# PM6680_OCXO.net
KiCad netlist of a schematic drawn in Altium Designer
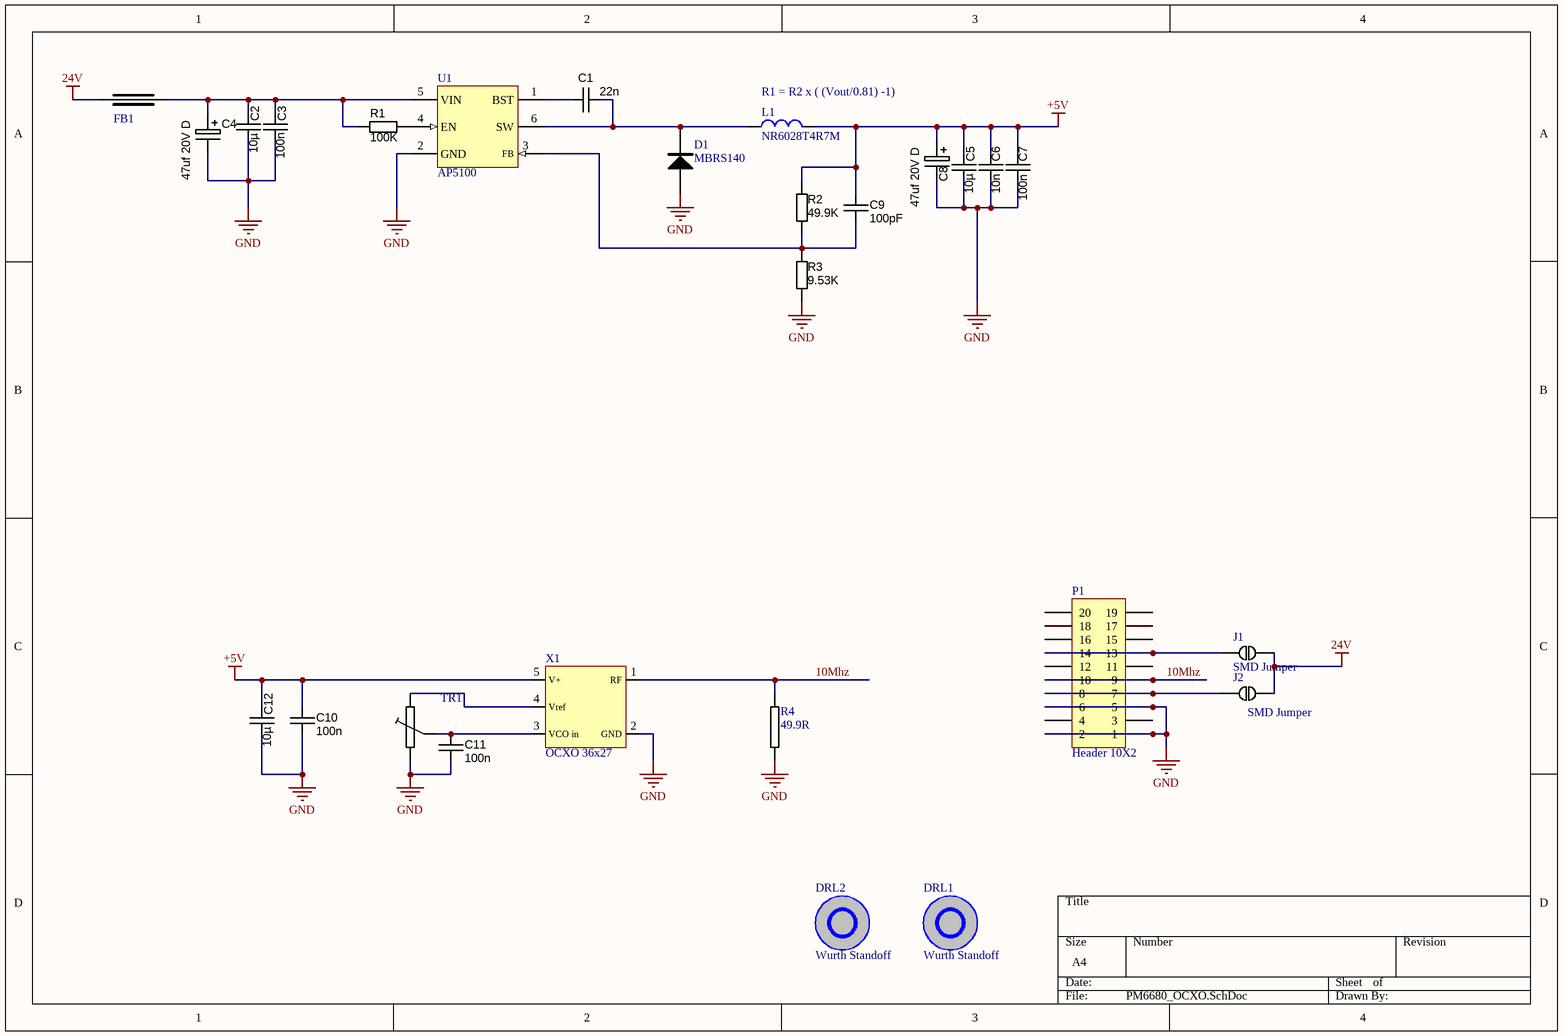
[diagram p0: PM6680_OCXO.SchDoc]

(export (version "E")
  (design (tool "Eeschema 10.0.6"))
  (components
    (comp (ref "C1")
      (value "22n")
      (footprint "CAPC1608N")
      (description "Capacitor SMD Cer 10pF 5% 50V NP0 0603")
      (fields (field (name "TOLERANCE") "±5%") (field (name "PART") "C0603X104K5RAC"))
      (libsource (lib "PBL - Capacitors") (part "CAPC_10p_0603_NP0_1%_50V"))
    )
    (comp (ref "C2")
      (value "10µ")
      (footprint "CAPC3225N")
      (description "Capacitor SMD Cer 10uF 20% 16V X5R 1210")
      (fields (field (name "TOLERANCE") "±20%"))
      (libsource (lib "PBL - Capacitors") (part "CAPC_10u_1210_50V"))
    )
    (comp (ref "C3")
      (value "100n")
      (footprint "CAPC1608N")
      (description "Capacitor SMD Cer 10pF 5% 50V NP0 0603")
      (fields (field (name "TOLERANCE") "±5%") (field (name "PART") "C0603X104K5RAC"))
      (libsource (lib "PBL - Capacitors") (part "CAPC_10p_0603_NP0_1%_50V"))
    )
    (comp (ref "C4")
      (value "47uf 20V D")
      (footprint "CAPMP7343X310N")
      (description "Capacitor SMD Tant 330uF 20% 6V3 2917")
      (fields
        (field (name "TOLERANCE") "±20%")
        (field (name "MANUFACTURER PART NUMBER") "T520D337M006ATE015")
      )
      (libsource (lib "PBL - Capacitors") (part "CAPT_330u_2917_6V3"))
    )
    (comp (ref "C5")
      (value "10µ")
      (footprint "CAPC3225N")
      (description "Capacitor SMD Cer 10uF 20% 16V X5R 1210")
      (fields (field (name "TOLERANCE") "±20%"))
      (libsource (lib "PBL - Capacitors") (part "CAPC_10u_1210_50V"))
    )
    (comp (ref "C6")
      (value "10n")
      (footprint "CAPC1608N")
      (description "Capacitor SMD Cer 10pF 5% 50V NP0 0603")
      (fields (field (name "TOLERANCE") "±5%") (field (name "PART") "C0603X104K5RAC"))
      (libsource (lib "PBL - Capacitors") (part "CAPC_10p_0603_NP0_1%_50V"))
    )
    (comp (ref "C7")
      (value "100n")
      (footprint "CAPC1608N")
      (description "Capacitor SMD Cer 10pF 5% 50V NP0 0603")
      (fields (field (name "TOLERANCE") "±5%") (field (name "PART") "C0603X104K5RAC"))
      (libsource (lib "PBL - Capacitors") (part "CAPC_10p_0603_NP0_1%_50V"))
    )
    (comp (ref "C8")
      (value "47uf 20V D")
      (footprint "CAPMP7343X310N")
      (description "Capacitor SMD Tant 330uF 20% 6V3 2917")
      (fields
        (field (name "TOLERANCE") "±20%")
        (field (name "MANUFACTURER PART NUMBER") "T520D337M006ATE015")
      )
      (libsource (lib "PBL - Capacitors") (part "CAPT_330u_2917_6V3"))
    )
    (comp (ref "C9")
      (value "100pF")
      (footprint "CAPC1608N")
      (description "Capacitor SMD Cer 10pF 5% 50V NP0 0603")
      (fields (field (name "TOLERANCE") "±5%") (field (name "PART") "C0603X104K5RAC"))
      (libsource (lib "PBL - Capacitors") (part "CAPC_10p_0603_NP0_1%_50V"))
    )
    (comp (ref "C10")
      (value "100n")
      (footprint "CAPC1608N")
      (description "Capacitor SMD Cer 10pF 5% 50V NP0 0603")
      (fields (field (name "TOLERANCE") "±5%") (field (name "PART") "C0603X104K5RAC"))
      (libsource (lib "PBL - Capacitors") (part "CAPC_10p_0603_NP0_1%_50V"))
    )
    (comp (ref "C11")
      (value "100n")
      (footprint "CAPC1608N")
      (description "Capacitor SMD Cer 10pF 5% 50V NP0 0603")
      (fields (field (name "TOLERANCE") "±5%") (field (name "PART") "C0603X104K5RAC"))
      (libsource (lib "PBL - Capacitors") (part "CAPC_10p_0603_NP0_1%_50V"))
    )
    (comp (ref "C12")
      (value "10µ")
      (footprint "CAPC3225N")
      (description "Capacitor SMD Cer 10uF 20% 16V X5R 1210")
      (fields (field (name "TOLERANCE") "±20%"))
      (libsource (lib "PBL - Capacitors") (part "CAPC_10u_1210_50V"))
    )
    (comp (ref "D1")
      (value "MBRS140")
      (footprint "DIODE-SMA")
      (description "DIODE")
      (libsource (lib "Generic") (part "MBRS140"))
    )
    (comp (ref "DRL1")
      (value "Wurth Standoff")
      (footprint "Wurth_PCB_STANDOFF_7740_6mm")
      (fields (field (name "PART") "9774050360"))
      (libsource (lib "cvlib") (part "PCB_Sandoff"))
    )
    (comp (ref "DRL2")
      (value "Wurth Standoff")
      (footprint "Wurth_PCB_STANDOFF_7740_6mm")
      (fields (field (name "PART") "9774050360"))
      (libsource (lib "cvlib") (part "PCB_Sandoff"))
    )
    (comp (ref "FB1")
      (value "~")
      (footprint "0805FB-600Z")
      (description "FERRITE BEAD 600 OHM 2A")
      (fields (field (name "PART") "ILHB0805ER300V"))
      (libsource (lib "Generic") (part "0805FB-600Z"))
    )
    (comp (ref "J1")
      (value "SMD Jumper")
      (footprint "SMD_Jumper")
      (libsource (lib "cvlib") (part "SMD_Jumper"))
    )
    (comp (ref "J2")
      (value "SMD Jumper")
      (footprint "SMD_Jumper")
      (libsource (lib "cvlib") (part "SMD_Jumper"))
    )
    (comp (ref "L1")
      (value "NR6028T4R7M")
      (footprint "TAIYO_NR6028T4R7M")
      (libsource (lib "Inductor") (part "inductor_smd"))
    )
    (comp (ref "P1")
      (value "Header 10X2")
      (footprint "HDR2X10")
      (description "Header, 10-Pin, Dual row")
      (fields (field (name "PUBLISHER") "Altium Limited"))
      (libsource (lib "Miscellaneous Connectors") (part "Header 10X2"))
    )
    (comp (ref "R1")
      (value "100K")
      (footprint "RESC1608N_ZERO")
      (description "Resistor SMD chip 0.0 Ohm 0.1W 0603")
      (fields (field (name "TOLERANCE") "±5%") (field (name "Comment") "Thick Film"))
      (libsource (lib "PBL - Resistors") (part "RES_0R_0603"))
    )
    (comp (ref "R2")
      (value "49.9K")
      (footprint "RESC1608N_ZERO")
      (description "Resistor SMD chip 0.0 Ohm 0.1W 0603")
      (fields (field (name "TOLERANCE") "±5%") (field (name "Comment") "Thick Film"))
      (libsource (lib "") (part "RES_0R_0603_2"))
    )
    (comp (ref "R3")
      (value "9.53K")
      (footprint "RESC1608N_ZERO")
      (description "Resistor SMD chip 0.0 Ohm 0.1W 0603")
      (fields (field (name "TOLERANCE") "±5%") (field (name "Comment") "Thick Film"))
      (libsource (lib "") (part "RES_0R_0603_1"))
    )
    (comp (ref "R4")
      (value "49.9R")
      (footprint "0805R-5K6")
      (description "RESISTOR 0805 1/4 WATT THIN FILM")
      (fields (field (name "PART") "RK73H2ATTD2150F"))
      (libsource (lib "Generic") (part "0805R-5K6"))
    )
    (comp (ref "TR1")
      (value "~")
      (footprint "TRIMMER-MT")
      (description "TRIMMABLE RESISTOR")
      (fields (field (name "PART") "T93XA103KT20"))
      (libsource (lib "Generic") (part "THTRIM-GENERIC"))
    )
    (comp (ref "U1") (value "AP5100") (footprint "SOT23-6") (libsource (lib "cvlib") (part "AP5100")))
    (comp (ref "X1")
      (value "OCXO 36x27")
      (footprint "OCXO_Small")
      (fields (field (name "PART") "CTS 970"))
      (libsource (lib "cvlib") (part "OCXO_Small_Bliey_6891_isotemp_ocxo131"))
    )
  )
  (nets
    (net (code "1") (name "+5V") (class "Default")
      (node (ref "C10") (pin "1") (pintype "passive"))
      (node (ref "C12") (pin "1") (pintype "passive"))
      (node (ref "C5") (pin "1") (pintype "passive"))
      (node (ref "C6") (pin "1") (pintype "passive"))
      (node (ref "C7") (pin "1") (pintype "passive"))
      (node (ref "C8") (pin "1") (pintype "passive"))
      (node (ref "C9") (pin "1") (pintype "passive"))
      (node (ref "L1") (pin "2") (pinfunction "2_2") (pintype "passive"))
      (node (ref "R2") (pin "1") (pinfunction "1_1") (pintype "passive"))
      (node (ref "X1") (pin "5") (pinfunction "V+_5") (pintype "passive"))
    )
    (net (code "2") (name "/10Mhz") (class "Default")
      (node (ref "P1") (pin "10") (pinfunction "10_10") (pintype "passive"))
      (node (ref "P1") (pin "9") (pinfunction "9_9") (pintype "passive"))
      (node (ref "R4") (pin "1") (pintype "passive"))
      (node (ref "X1") (pin "1") (pinfunction "RF_1") (pintype "passive"))
    )
    (net (code "3") (name "24V") (class "Default")
      (node (ref "FB1") (pin "1") (pintype "passive"))
      (node (ref "J1") (pin "2") (pinfunction "2_2") (pintype "passive"))
      (node (ref "J2") (pin "2") (pinfunction "2_2") (pintype "passive"))
    )
    (net (code "4") (name "GND") (class "Default")
      (node (ref "C10") (pin "2") (pintype "passive"))
      (node (ref "C11") (pin "2") (pintype "passive"))
      (node (ref "C12") (pin "2") (pintype "passive"))
      (node (ref "C2") (pin "2") (pintype "passive"))
      (node (ref "C3") (pin "2") (pintype "passive"))
      (node (ref "C4") (pin "2") (pintype "passive"))
      (node (ref "C5") (pin "2") (pintype "passive"))
      (node (ref "C6") (pin "2") (pintype "passive"))
      (node (ref "C7") (pin "2") (pintype "passive"))
      (node (ref "C8") (pin "2") (pintype "passive"))
      (node (ref "D1") (pin "A") (pinfunction "A_A") (pintype "passive"))
      (node (ref "P1") (pin "1") (pinfunction "1_1") (pintype "passive"))
      (node (ref "P1") (pin "2") (pinfunction "2_2") (pintype "passive"))
      (node (ref "P1") (pin "5") (pinfunction "5_5") (pintype "passive"))
      (node (ref "P1") (pin "6") (pinfunction "6_6") (pintype "passive"))
      (node (ref "R3") (pin "1") (pinfunction "1_1") (pintype "passive"))
      (node (ref "R4") (pin "2") (pintype "passive"))
      (node (ref "TR1") (pin "1") (pinfunction "1_1") (pintype "passive"))
      (node (ref "U1") (pin "2") (pinfunction "GND_2") (pintype "power_in"))
      (node (ref "X1") (pin "2") (pinfunction "GND_2") (pintype "passive"))
    )
    (net (code "5") (name "Net-(J1-Pad1)") (class "Default")
      (node (ref "J1") (pin "1") (pinfunction "1_1") (pintype "passive"))
      (node (ref "P1") (pin "13") (pinfunction "13_13") (pintype "passive"))
      (node (ref "P1") (pin "14") (pinfunction "14_14") (pintype "passive"))
    )
    (net (code "6") (name "Net-(J2-Pad1)") (class "Default")
      (node (ref "J2") (pin "1") (pinfunction "1_1") (pintype "passive"))
      (node (ref "P1") (pin "7") (pinfunction "7_7") (pintype "passive"))
      (node (ref "P1") (pin "8") (pinfunction "8_8") (pintype "passive"))
    )
    (net (code "7") (name "Net-(U1-BST)") (class "Default")
      (node (ref "C1") (pin "2") (pintype "passive"))
      (node (ref "U1") (pin "1") (pinfunction "BST_1") (pintype "power_in"))
    )
    (net (code "8") (name "Net-(U1-EN)") (class "Default")
      (node (ref "R1") (pin "2") (pinfunction "2_2") (pintype "passive"))
      (node (ref "U1") (pin "4") (pinfunction "EN_4") (pintype "input"))
    )
    (net (code "9") (name "Net-(U1-FB)") (class "Default")
      (node (ref "C9") (pin "2") (pintype "passive"))
      (node (ref "R2") (pin "2") (pinfunction "2_2") (pintype "passive"))
      (node (ref "R3") (pin "2") (pinfunction "2_2") (pintype "passive"))
      (node (ref "U1") (pin "3") (pinfunction "FB_3") (pintype "input"))
    )
    (net (code "10") (name "Net-(U1-SW)") (class "Default")
      (node (ref "C1") (pin "1") (pintype "passive"))
      (node (ref "D1") (pin "K") (pinfunction "K_K") (pintype "passive"))
      (node (ref "L1") (pin "1") (pinfunction "1_1") (pintype "passive"))
      (node (ref "U1") (pin "6") (pinfunction "SW_6") (pintype "passive"))
    )
    (net (code "11") (name "Net-(U1-VIN)") (class "Default")
      (node (ref "C2") (pin "1") (pintype "passive"))
      (node (ref "C3") (pin "1") (pintype "passive"))
      (node (ref "C4") (pin "1") (pintype "passive"))
      (node (ref "FB1") (pin "2") (pintype "passive"))
      (node (ref "R1") (pin "1") (pinfunction "1_1") (pintype "passive"))
      (node (ref "U1") (pin "5") (pinfunction "VIN_5") (pintype "power_in"))
    )
    (net (code "12") (name "Net-(X1-VCO_in)") (class "Default")
      (node (ref "C11") (pin "1") (pintype "passive"))
      (node (ref "TR1") (pin "W") (pinfunction "W_W") (pintype "passive"))
      (node (ref "X1") (pin "3") (pinfunction "VCO_in_3") (pintype "passive"))
    )
    (net (code "13") (name "Net-(X1-Vref)") (class "Default")
      (node (ref "TR1") (pin "2") (pinfunction "2_2") (pintype "passive"))
      (node (ref "X1") (pin "4") (pinfunction "Vref_4") (pintype "passive"))
    )
    (net (code "14") (name "unconnected-(P1-Pad3)") (class "Default")
      (node (ref "P1") (pin "3") (pinfunction "3_3") (pintype "passive"))
    )
    (net (code "15") (name "unconnected-(P1-Pad4)") (class "Default")
      (node (ref "P1") (pin "4") (pinfunction "4_4") (pintype "passive"))
    )
    (net (code "16") (name "unconnected-(P1-Pad11)") (class "Default")
      (node (ref "P1") (pin "11") (pinfunction "11_11") (pintype "passive"))
    )
    (net (code "17") (name "unconnected-(P1-Pad12)") (class "Default")
      (node (ref "P1") (pin "12") (pinfunction "12_12") (pintype "passive"))
    )
    (net (code "18") (name "unconnected-(P1-Pad15)") (class "Default")
      (node (ref "P1") (pin "15") (pinfunction "15_15") (pintype "passive"))
    )
    (net (code "19") (name "unconnected-(P1-Pad16)") (class "Default")
      (node (ref "P1") (pin "16") (pinfunction "16_16") (pintype "passive"))
    )
    (net (code "20") (name "unconnected-(P1-Pad17)") (class "Default")
      (node (ref "P1") (pin "17") (pinfunction "17_17") (pintype "passive"))
    )
    (net (code "21") (name "unconnected-(P1-Pad18)") (class "Default")
      (node (ref "P1") (pin "18") (pinfunction "18_18") (pintype "passive"))
    )
    (net (code "22") (name "unconnected-(P1-Pad19)") (class "Default")
      (node (ref "P1") (pin "19") (pinfunction "19_19") (pintype "passive"))
    )
    (net (code "23") (name "unconnected-(P1-Pad20)") (class "Default")
      (node (ref "P1") (pin "20") (pinfunction "20_20") (pintype "passive"))
    )
  )
)
